# RF.net
KiCad netlist of a schematic drawn in Altium Designer
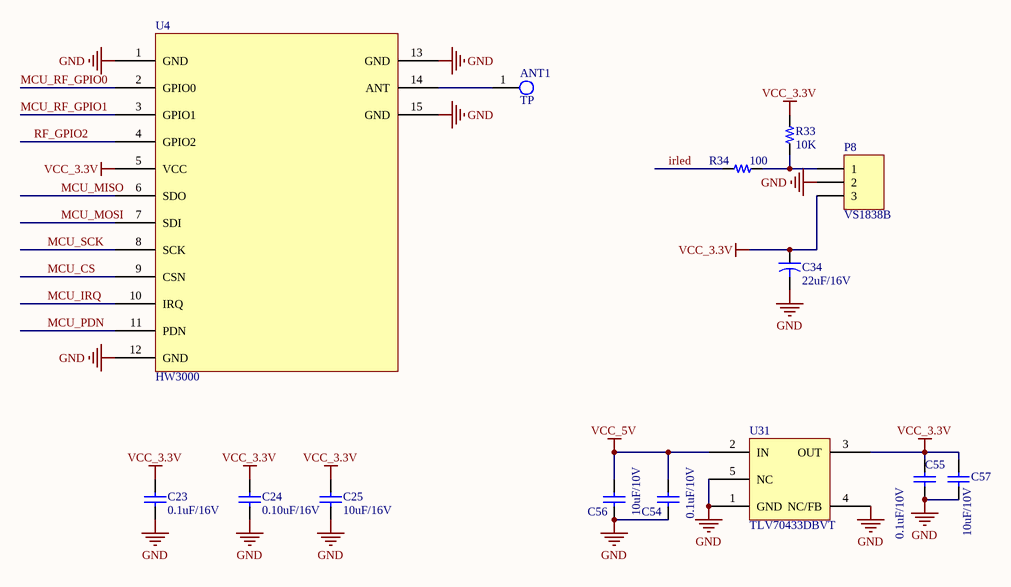
[diagram p0: RF.SchDoc]

(export (version "E")
  (design (tool "Eeschema 10.0.6"))
  (components
    (comp (ref "ANT1") (value "TP") (footprint "ANT_TH") (libsource (lib "Schlib_20110825") (part "TP")))
    (comp (ref "C23")
      (value "0.1uF/16V")
      (footprint "0603C")
      (description "Capacitor")
      (fields (field (name "PUBLISHER") "Altium Limited"))
      (libsource (lib "Miscellaneous Devices") (part "Cap"))
    )
    (comp (ref "C24")
      (value "0.10uF/16V")
      (footprint "0603C")
      (description "Capacitor")
      (fields (field (name "PUBLISHER") "Altium Limited"))
      (libsource (lib "Miscellaneous Devices") (part "Cap"))
    )
    (comp (ref "C25")
      (value "10uF/16V")
      (footprint "0603C")
      (description "Capacitor")
      (fields (field (name "PUBLISHER") "Altium Limited"))
      (libsource (lib "Miscellaneous Devices") (part "Cap"))
    )
    (comp (ref "C34")
      (value "22uF/16V")
      (footprint "0805C")
      (description "Capacitor")
      (fields (field (name "PUBLISHER") "Altium Limited"))
      (libsource (lib "Miscellaneous Devices") (part "Cap2"))
    )
    (comp (ref "C54")
      (value "0.1uF/10V")
      (footprint "0603C")
      (description "Capacitor")
      (fields (field (name "PUBLISHER") "Altium Limited"))
      (libsource (lib "Miscellaneous Devices") (part "Cap"))
    )
    (comp (ref "C55")
      (value "0.1uF/10V")
      (footprint "0603C")
      (description "Capacitor")
      (fields (field (name "PUBLISHER") "Altium Limited"))
      (libsource (lib "Miscellaneous Devices") (part "Cap"))
    )
    (comp (ref "C56")
      (value "10uF/10V")
      (footprint "0603C")
      (description "Capacitor")
      (fields (field (name "PUBLISHER") "Altium Limited"))
      (libsource (lib "Miscellaneous Devices") (part "Cap"))
    )
    (comp (ref "C57")
      (value "10uF/10V")
      (footprint "0603C")
      (description "Capacitor")
      (fields (field (name "PUBLISHER") "Altium Limited"))
      (libsource (lib "Miscellaneous Devices") (part "Cap"))
    )
    (comp (ref "P8")
      (value "VS1838B")
      (footprint "VS1838B")
      (description "Header, 3-Pin")
      (fields (field (name "PUBLISHER") "Altium Limited"))
      (libsource (lib "Miscellaneous Connectors") (part "Header 3"))
    )
    (comp (ref "R33")
      (value "10K")
      (footprint "0603R")
      (description "R")
      (libsource (lib "JRJ_1") (part "R"))
    )
    (comp (ref "R34")
      (value "100")
      (footprint "0603R")
      (description "R")
      (libsource (lib "JRJ_1") (part "R"))
    )
    (comp (ref "U4")
      (value "HW3000")
      (footprint "HW3000")
      (libsource (lib "Schlib_20110825") (part "HW3000"))
    )
    (comp (ref "U31")
      (value "TLV70433DBVT")
      (footprint "SOT23-5(DBV)")
      (libsource (lib "JRJ") (part "TPS76318"))
    )
  )
  (nets
    (net (code "1") (name "/MCU_CS") (class "Default")
      (node (ref "U4") (pin "9") (pinfunction "CSN_9") (pintype "passive"))
    )
    (net (code "2") (name "/MCU_IRQ") (class "Default")
      (node (ref "U4") (pin "10") (pinfunction "IRQ_10") (pintype "passive"))
    )
    (net (code "3") (name "/MCU_MISO") (class "Default")
      (node (ref "U4") (pin "6") (pinfunction "SDO_6") (pintype "passive"))
    )
    (net (code "4") (name "/MCU_MOSI") (class "Default")
      (node (ref "U4") (pin "7") (pinfunction "SDI_7") (pintype "passive"))
    )
    (net (code "5") (name "/MCU_PDN") (class "Default")
      (node (ref "U4") (pin "11") (pinfunction "PDN_11") (pintype "passive"))
    )
    (net (code "6") (name "/MCU_RF_GPIO0") (class "Default")
      (node (ref "U4") (pin "2") (pinfunction "GPIO0_2") (pintype "passive"))
    )
    (net (code "7") (name "/MCU_RF_GPIO1") (class "Default")
      (node (ref "U4") (pin "3") (pinfunction "GPIO1_3") (pintype "passive"))
    )
    (net (code "8") (name "/MCU_SCK") (class "Default")
      (node (ref "U4") (pin "8") (pinfunction "SCK_8") (pintype "passive"))
    )
    (net (code "9") (name "/RF_GPIO2") (class "Default")
      (node (ref "U4") (pin "4") (pinfunction "GPIO2_4") (pintype "passive"))
    )
    (net (code "10") (name "/irled") (class "Default") (node (ref "R34") (pin "2") (pintype "passive")))
    (net (code "11") (name "GND") (class "Default")
      (node (ref "C23") (pin "2") (pinfunction "2_2") (pintype "passive"))
      (node (ref "C24") (pin "2") (pinfunction "2_2") (pintype "passive"))
      (node (ref "C25") (pin "2") (pinfunction "2_2") (pintype "passive"))
      (node (ref "C34") (pin "2") (pinfunction "2_2") (pintype "passive"))
      (node (ref "C54") (pin "2") (pinfunction "2_2") (pintype "passive"))
      (node (ref "C55") (pin "2") (pinfunction "2_2") (pintype "passive"))
      (node (ref "C56") (pin "1") (pinfunction "1_1") (pintype "passive"))
      (node (ref "C57") (pin "1") (pinfunction "1_1") (pintype "passive"))
      (node (ref "P8") (pin "2") (pinfunction "2_2") (pintype "passive"))
      (node (ref "U31") (pin "1") (pinfunction "GND_1") (pintype "passive"))
      (node (ref "U31") (pin "4") (pinfunction "NC/FB_4") (pintype "passive"))
      (node (ref "U31") (pin "5") (pinfunction "NC_5") (pintype "passive"))
      (node (ref "U4") (pin "1") (pinfunction "GND_1") (pintype "passive"))
      (node (ref "U4") (pin "12") (pinfunction "GND_12") (pintype "passive"))
      (node (ref "U4") (pin "13") (pinfunction "GND_13") (pintype "passive"))
      (node (ref "U4") (pin "15") (pinfunction "GND_15") (pintype "passive"))
    )
    (net (code "12") (name "Net-(P8-Pad1)") (class "Default")
      (node (ref "P8") (pin "1") (pinfunction "1_1") (pintype "passive"))
      (node (ref "R33") (pin "1") (pintype "passive"))
      (node (ref "R34") (pin "1") (pintype "passive"))
    )
    (net (code "13") (name "Net-(U4-ANT)") (class "Default")
      (node (ref "ANT1") (pin "1") (pintype "passive"))
      (node (ref "U4") (pin "14") (pinfunction "ANT_14") (pintype "passive"))
    )
    (net (code "14") (name "VCC_3.3V") (class "Default")
      (node (ref "C23") (pin "1") (pinfunction "1_1") (pintype "passive"))
      (node (ref "C24") (pin "1") (pinfunction "1_1") (pintype "passive"))
      (node (ref "C25") (pin "1") (pinfunction "1_1") (pintype "passive"))
      (node (ref "C34") (pin "1") (pinfunction "1_1") (pintype "passive"))
      (node (ref "C55") (pin "1") (pinfunction "1_1") (pintype "passive"))
      (node (ref "C57") (pin "2") (pinfunction "2_2") (pintype "passive"))
      (node (ref "P8") (pin "3") (pinfunction "3_3") (pintype "passive"))
      (node (ref "R33") (pin "2") (pintype "passive"))
      (node (ref "U31") (pin "3") (pinfunction "OUT_3") (pintype "passive"))
      (node (ref "U4") (pin "5") (pinfunction "VCC_5") (pintype "passive"))
    )
    (net (code "15") (name "VCC_5V") (class "Default")
      (node (ref "C54") (pin "1") (pinfunction "1_1") (pintype "passive"))
      (node (ref "C56") (pin "2") (pinfunction "2_2") (pintype "passive"))
      (node (ref "U31") (pin "2") (pinfunction "IN_2") (pintype "passive"))
    )
  )
)
